# EEPROM.net
KiCad netlist of a schematic drawn in Altium Designer
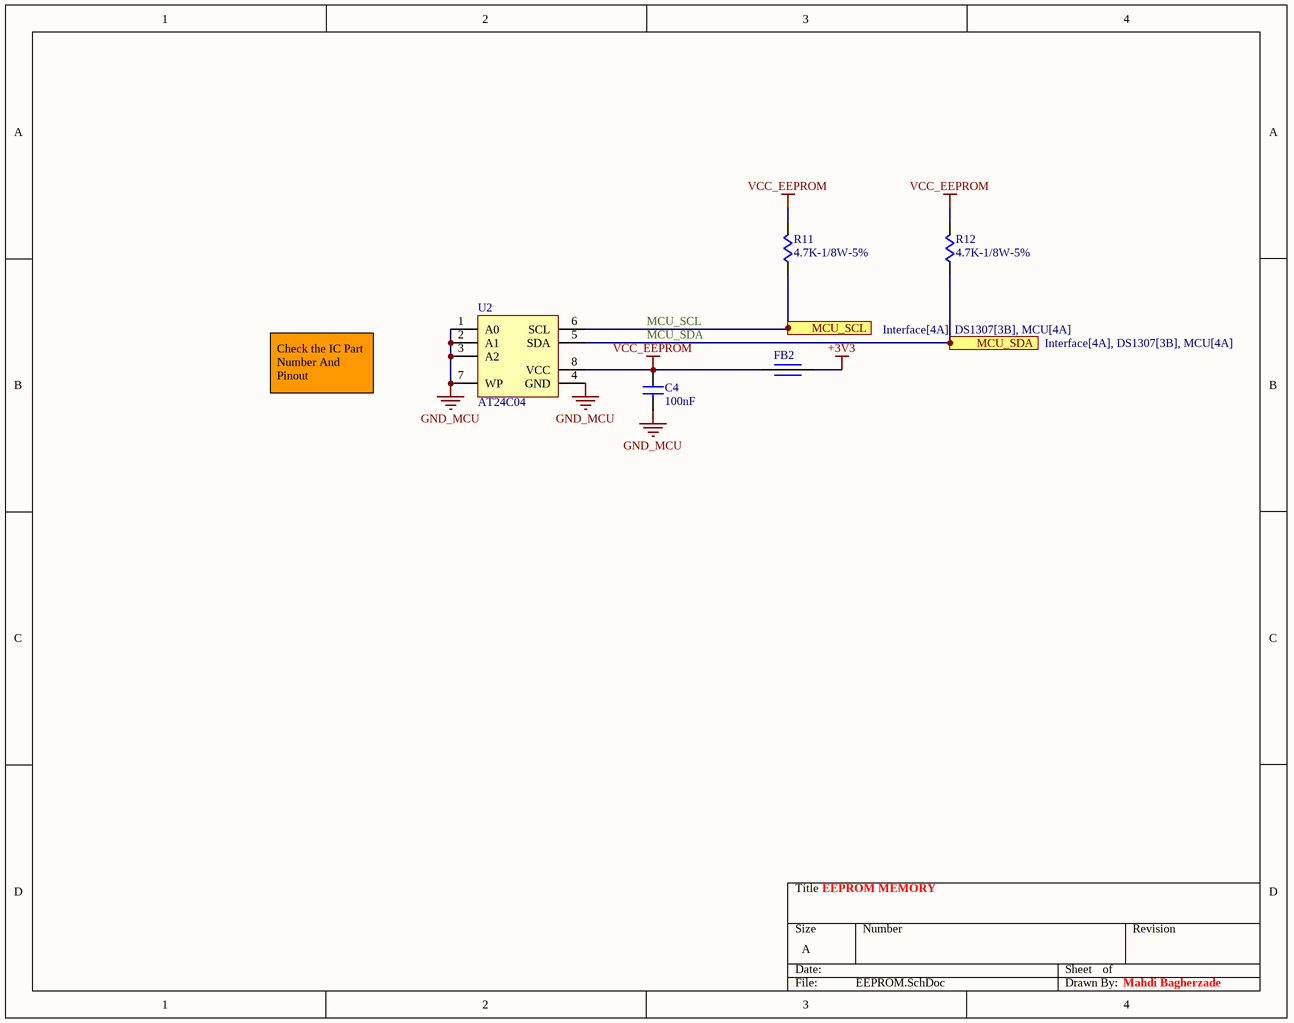
[diagram p0: EEPROM.SchDoc]

(export (version "E")
  (design (tool "Eeschema 10.0.6"))
  (components
    (comp (ref "C4")
      (value "100nF")
      (footprint "C-0805")
      (description "CAPACITOR")
      (fields
        (field (name "VOLTAGE") "50V")
        (field (name "TOLERANCE") "X7R")
        (field (name "PUBLISHER") "Mahdi Bagherzadeh")
      )
      (libsource (lib "Mahdi-Bagherzadeh") (part "CAP-CER"))
    )
    (comp (ref "FB2")
      (value "FERRITE BEAD")
      (footprint "FB-0805")
      (description "INDUCATOR")
      (fields (field (name "PUBLISHER") "Mahdi Bagherzadeh"))
      (libsource (lib "Mahdi-Bagherzadeh") (part "FERRITE BEAD"))
    )
    (comp (ref "R11")
      (value "4.7K-1/8W-5%")
      (footprint "R-0805")
      (description "RESISTOR")
      (fields (field (name "PUBLISHER") "Mahdi Bagherzadeh"))
      (libsource (lib "Mahdi-Bagherzadeh") (part "RES"))
    )
    (comp (ref "R12")
      (value "4.7K-1/8W-5%")
      (footprint "R-0805")
      (description "RESISTOR")
      (fields (field (name "PUBLISHER") "Mahdi Bagherzadeh"))
      (libsource (lib "Mahdi-Bagherzadeh") (part "RES"))
    )
    (comp (ref "U2")
      (value "AT24C04")
      (footprint "SOIC8")
      (description "IC")
      (fields (field (name "PUBLISHER") "Mahdi Bagherzadeh"))
      (libsource (lib "Mahdi-Bagherzadeh") (part "AT24C04"))
    )
  )
  (nets
    (net (code "1") (name "+3V3") (class "Default")
      (node (ref "FB2") (pin "2") (pinfunction "2_2") (pintype "passive"))
    )
    (net (code "2") (name "/MCU_SCL") (class "Default")
      (node (ref "R11") (pin "1") (pinfunction "1_1") (pintype "passive"))
      (node (ref "U2") (pin "6") (pinfunction "SCL_6") (pintype "passive"))
    )
    (net (code "3") (name "/MCU_SDA") (class "Default")
      (node (ref "R12") (pin "1") (pinfunction "1_1") (pintype "passive"))
      (node (ref "U2") (pin "5") (pinfunction "SDA_5") (pintype "passive"))
    )
    (net (code "4") (name "GND_MCU") (class "Default")
      (node (ref "C4") (pin "2") (pinfunction "2_2") (pintype "passive"))
      (node (ref "U2") (pin "1") (pinfunction "A0_1") (pintype "passive"))
      (node (ref "U2") (pin "2") (pinfunction "A1_2") (pintype "passive"))
      (node (ref "U2") (pin "3") (pinfunction "A2_3") (pintype "passive"))
      (node (ref "U2") (pin "4") (pinfunction "GND_4") (pintype "passive"))
      (node (ref "U2") (pin "7") (pinfunction "WP_7") (pintype "passive"))
    )
    (net (code "5") (name "VCC_EEPROM") (class "Default")
      (node (ref "C4") (pin "1") (pinfunction "1_1") (pintype "passive"))
      (node (ref "FB2") (pin "1") (pinfunction "1_1") (pintype "passive"))
      (node (ref "R11") (pin "2") (pinfunction "2_2") (pintype "passive"))
      (node (ref "R12") (pin "2") (pinfunction "2_2") (pintype "passive"))
      (node (ref "U2") (pin "8") (pinfunction "VCC_8") (pintype "passive"))
    )
  )
)
